# sch.net
KiCad netlist of a schematic drawn in EasyEDA
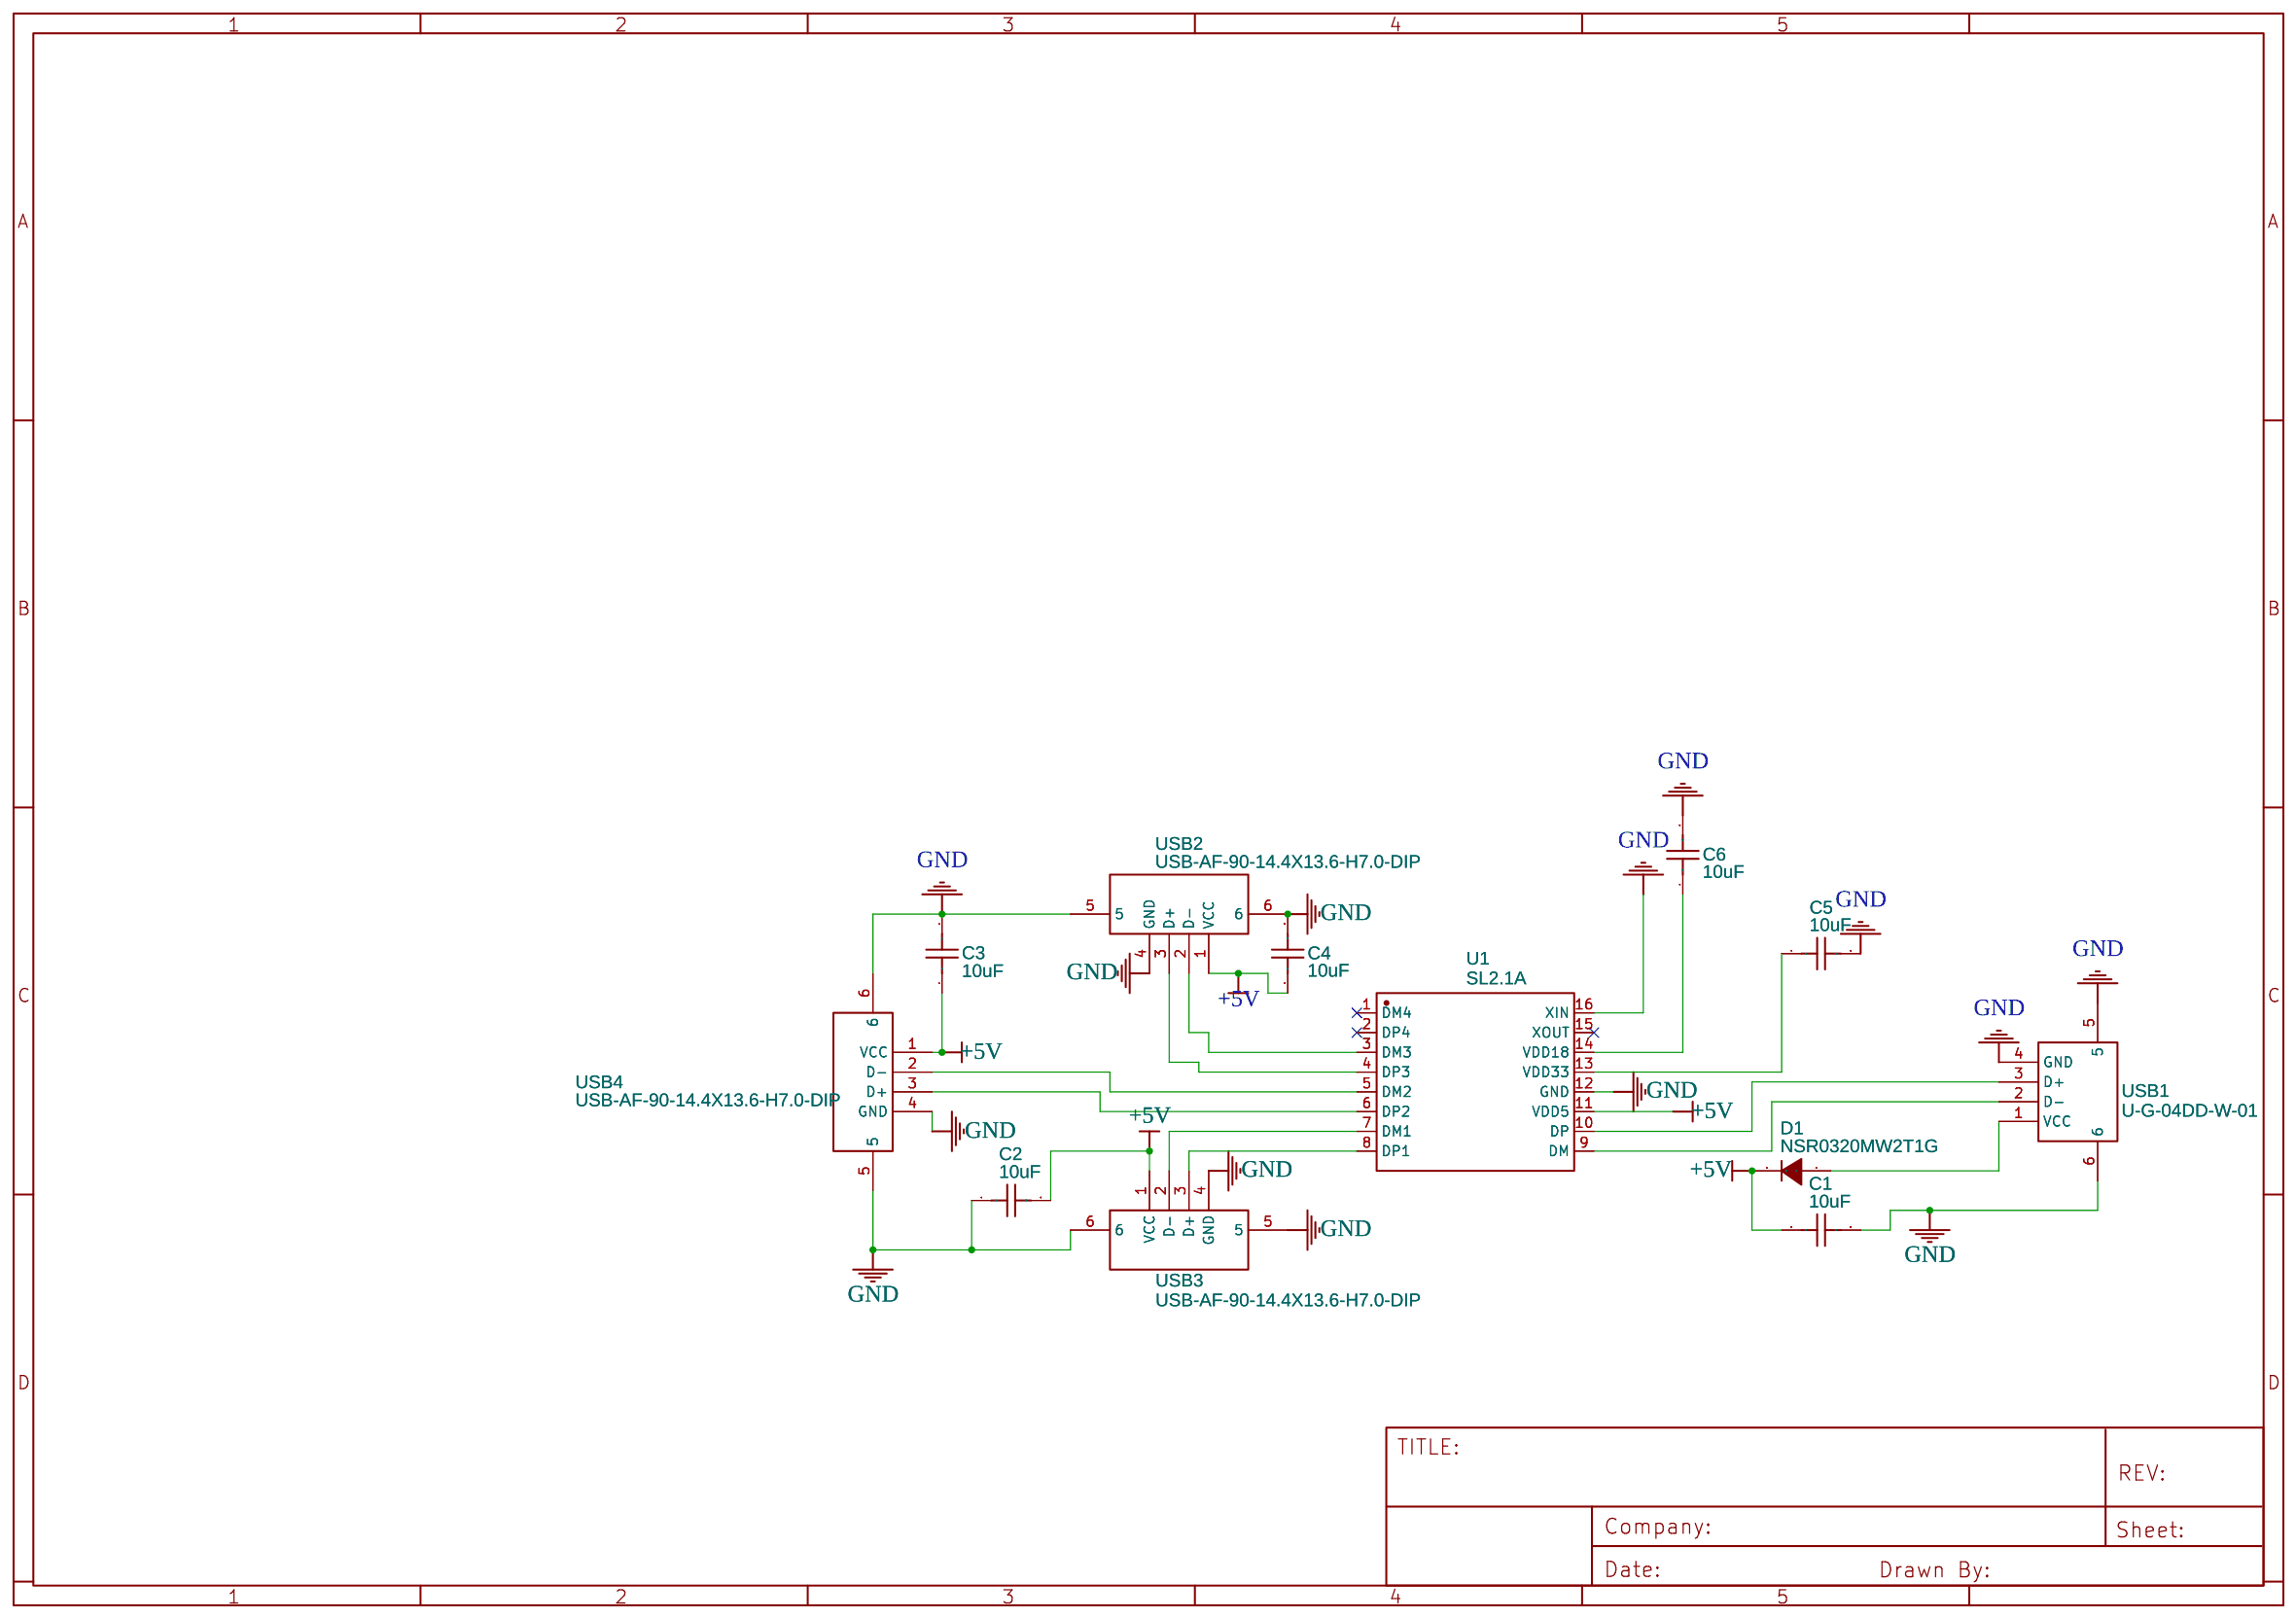
[diagram p0: schematic sheet]

(export (version "E")
  (design (tool "Eeschema 10.0.6"))
  (components
    (comp (ref "C1")
      (value "10uF")
      (fields
        (field (name "Manufacturer Part") "CL10A106KP8NNNC")
        (field (name "Manufacturer") "SAMSUNG(三星)")
      )
      (libsource (lib "") (part "CL10A106KP8NNNC_1"))
    )
    (comp (ref "C2")
      (value "10uF")
      (fields
        (field (name "Manufacturer Part") "CL10A106KP8NNNC")
        (field (name "Manufacturer") "SAMSUNG(三星)")
      )
      (libsource (lib "") (part "CL10A106KP8NNNC_1"))
    )
    (comp (ref "C3")
      (value "10uF")
      (fields
        (field (name "Manufacturer Part") "CL10A106KP8NNNC")
        (field (name "Manufacturer") "SAMSUNG(三星)")
      )
      (libsource (lib "") (part "CL10A106KP8NNNC"))
    )
    (comp (ref "C4")
      (value "10uF")
      (fields
        (field (name "Manufacturer Part") "CL10A106KP8NNNC")
        (field (name "Manufacturer") "SAMSUNG(三星)")
      )
      (libsource (lib "") (part "CL10A106KP8NNNC"))
    )
    (comp (ref "C5")
      (value "10uF")
      (fields
        (field (name "Manufacturer Part") "CL10A106KP8NNNC")
        (field (name "Manufacturer") "SAMSUNG(三星)")
      )
      (libsource (lib "") (part "CL10A106KP8NNNC_1"))
    )
    (comp (ref "C6")
      (value "10uF")
      (fields
        (field (name "Manufacturer Part") "CL10A106KP8NNNC")
        (field (name "Manufacturer") "SAMSUNG(三星)")
      )
      (libsource (lib "") (part "CL10A106KP8NNNC"))
    )
    (comp (ref "D1")
      (value "NSR0320MW2T1G")
      (fields (field (name "Manufacturer") "onsemi(安森美)"))
      (libsource (lib "") (part "NSR0320MW2T1G"))
    )
    (comp (ref "U1")
      (value "SL2.1A")
      (fields (field (name "Manufacturer") "CoreChips(和芯润德)"))
      (libsource (lib "") (part "SL2.1A"))
    )
    (comp (ref "USB1")
      (value "U-G-04DD-W-01")
      (fields (field (name "Manufacturer Part") "U-G-O4DD-W-1") (field (name "Manufacturer") "韩国韩荣"))
      (libsource (lib "") (part "U-G-04DD-W-01"))
    )
    (comp (ref "USB2")
      (value "USB-AF-90-14.4X13.6-H7.0-DIP")
      (fields (field (name "Manufacturer Part") "903-131A1011D10100") (field (name "Manufacturer") "精拓金"))
      (libsource (lib "") (part "USB-AF-90-14.4X13.6-H7.0-DIP_1"))
    )
    (comp (ref "USB3")
      (value "USB-AF-90-14.4X13.6-H7.0-DIP")
      (fields (field (name "Manufacturer Part") "903-131A1011D10100") (field (name "Manufacturer") "精拓金"))
      (libsource (lib "") (part "USB-AF-90-14.4X13.6-H7.0-DIP"))
    )
    (comp (ref "USB4")
      (value "USB-AF-90-14.4X13.6-H7.0-DIP")
      (fields (field (name "Manufacturer Part") "903-131A1011D10100") (field (name "Manufacturer") "精拓金"))
      (libsource (lib "") (part "USB-AF-90-14.4X13.6-H7.0-DIP_2"))
    )
  )
  (nets
    (net (code "1") (name "+5V") (class "Default")
      (node (ref "C1") (pin "1") (pinfunction "1_1") (pintype "unspecified"))
      (node (ref "C2") (pin "2") (pinfunction "2_2") (pintype "unspecified"))
      (node (ref "C3") (pin "1") (pinfunction "1_1") (pintype "unspecified"))
      (node (ref "C4") (pin "1") (pinfunction "1_1") (pintype "unspecified"))
      (node (ref "D1") (pin "1") (pinfunction "C_1") (pintype "unspecified"))
      (node (ref "U1") (pin "11") (pinfunction "VDD5_11") (pintype "unspecified"))
      (node (ref "USB2") (pin "1") (pinfunction "VCC_1") (pintype "unspecified"))
      (node (ref "USB3") (pin "1") (pinfunction "VCC_1") (pintype "unspecified"))
      (node (ref "USB4") (pin "1") (pinfunction "VCC_1") (pintype "unspecified"))
    )
    (net (code "2") (name "GND") (class "Default")
      (node (ref "C1") (pin "2") (pinfunction "2_2") (pintype "unspecified"))
      (node (ref "C2") (pin "1") (pinfunction "1_1") (pintype "unspecified"))
      (node (ref "C3") (pin "2") (pinfunction "2_2") (pintype "unspecified"))
      (node (ref "C4") (pin "2") (pinfunction "2_2") (pintype "unspecified"))
      (node (ref "C5") (pin "2") (pinfunction "2_2") (pintype "unspecified"))
      (node (ref "C6") (pin "2") (pinfunction "2_2") (pintype "unspecified"))
      (node (ref "U1") (pin "12") (pinfunction "GND_12") (pintype "unspecified"))
      (node (ref "U1") (pin "16") (pinfunction "XIN_16") (pintype "unspecified"))
      (node (ref "USB1") (pin "4") (pinfunction "GND_4") (pintype "unspecified"))
      (node (ref "USB1") (pin "5") (pinfunction "5_5") (pintype "unspecified"))
      (node (ref "USB1") (pin "6") (pinfunction "6_6") (pintype "unspecified"))
      (node (ref "USB2") (pin "4") (pinfunction "GND_4") (pintype "unspecified"))
      (node (ref "USB2") (pin "5") (pinfunction "5_5") (pintype "unspecified"))
      (node (ref "USB2") (pin "6") (pinfunction "6_6") (pintype "unspecified"))
      (node (ref "USB3") (pin "4") (pinfunction "GND_4") (pintype "unspecified"))
      (node (ref "USB3") (pin "5") (pinfunction "5_5") (pintype "unspecified"))
      (node (ref "USB3") (pin "6") (pinfunction "6_6") (pintype "unspecified"))
      (node (ref "USB4") (pin "4") (pinfunction "GND_4") (pintype "unspecified"))
      (node (ref "USB4") (pin "5") (pinfunction "5_5") (pintype "unspecified"))
      (node (ref "USB4") (pin "6") (pinfunction "6_6") (pintype "unspecified"))
    )
    (net (code "3") (name "Net-(D1-A)") (class "Default")
      (node (ref "D1") (pin "2") (pinfunction "A_2") (pintype "unspecified"))
      (node (ref "USB1") (pin "1") (pinfunction "VCC_1") (pintype "unspecified"))
    )
    (net (code "4") (name "Net-(U1-DM)") (class "Default")
      (node (ref "U1") (pin "9") (pinfunction "DM_9") (pintype "unspecified"))
      (node (ref "USB1") (pin "2") (pinfunction "D-_2") (pintype "unspecified"))
    )
    (net (code "5") (name "Net-(U1-DM1)") (class "Default")
      (node (ref "U1") (pin "7") (pinfunction "DM1_7") (pintype "unspecified"))
      (node (ref "USB3") (pin "2") (pinfunction "D-_2") (pintype "unspecified"))
    )
    (net (code "6") (name "Net-(U1-DM2)") (class "Default")
      (node (ref "U1") (pin "5") (pinfunction "DM2_5") (pintype "unspecified"))
      (node (ref "USB4") (pin "2") (pinfunction "D-_2") (pintype "unspecified"))
    )
    (net (code "7") (name "Net-(U1-DM3)") (class "Default")
      (node (ref "U1") (pin "3") (pinfunction "DM3_3") (pintype "unspecified"))
      (node (ref "USB2") (pin "2") (pinfunction "D-_2") (pintype "unspecified"))
    )
    (net (code "8") (name "Net-(U1-DP)") (class "Default")
      (node (ref "U1") (pin "10") (pinfunction "DP_10") (pintype "unspecified"))
      (node (ref "USB1") (pin "3") (pinfunction "D+_3") (pintype "unspecified"))
    )
    (net (code "9") (name "Net-(U1-DP1)") (class "Default")
      (node (ref "U1") (pin "8") (pinfunction "DP1_8") (pintype "unspecified"))
      (node (ref "USB3") (pin "3") (pinfunction "D+_3") (pintype "unspecified"))
    )
    (net (code "10") (name "Net-(U1-DP2)") (class "Default")
      (node (ref "U1") (pin "6") (pinfunction "DP2_6") (pintype "unspecified"))
      (node (ref "USB4") (pin "3") (pinfunction "D+_3") (pintype "unspecified"))
    )
    (net (code "11") (name "Net-(U1-DP3)") (class "Default")
      (node (ref "U1") (pin "4") (pinfunction "DP3_4") (pintype "unspecified"))
      (node (ref "USB2") (pin "3") (pinfunction "D+_3") (pintype "unspecified"))
    )
    (net (code "12") (name "Net-(U1-VDD18)") (class "Default")
      (node (ref "C6") (pin "1") (pinfunction "1_1") (pintype "unspecified"))
      (node (ref "U1") (pin "14") (pinfunction "VDD18_14") (pintype "unspecified"))
    )
    (net (code "13") (name "Net-(U1-VDD33)") (class "Default")
      (node (ref "C5") (pin "1") (pinfunction "1_1") (pintype "unspecified"))
      (node (ref "U1") (pin "13") (pinfunction "VDD33_13") (pintype "unspecified"))
    )
    (net (code "14") (name "unconnected-(U1-DM4-Pad1)") (class "Default")
      (node (ref "U1") (pin "1") (pinfunction "DM4_1") (pintype "unspecified+no_connect"))
    )
    (net (code "15") (name "unconnected-(U1-DP4-Pad2)") (class "Default")
      (node (ref "U1") (pin "2") (pinfunction "DP4_2") (pintype "unspecified+no_connect"))
    )
    (net (code "16") (name "unconnected-(U1-XOUT-Pad15)") (class "Default")
      (node (ref "U1") (pin "15") (pinfunction "XOUT_15") (pintype "unspecified+no_connect"))
    )
  )
)
